# equaliser_TDA7418.net
KiCad netlist of a schematic drawn in EAGLE
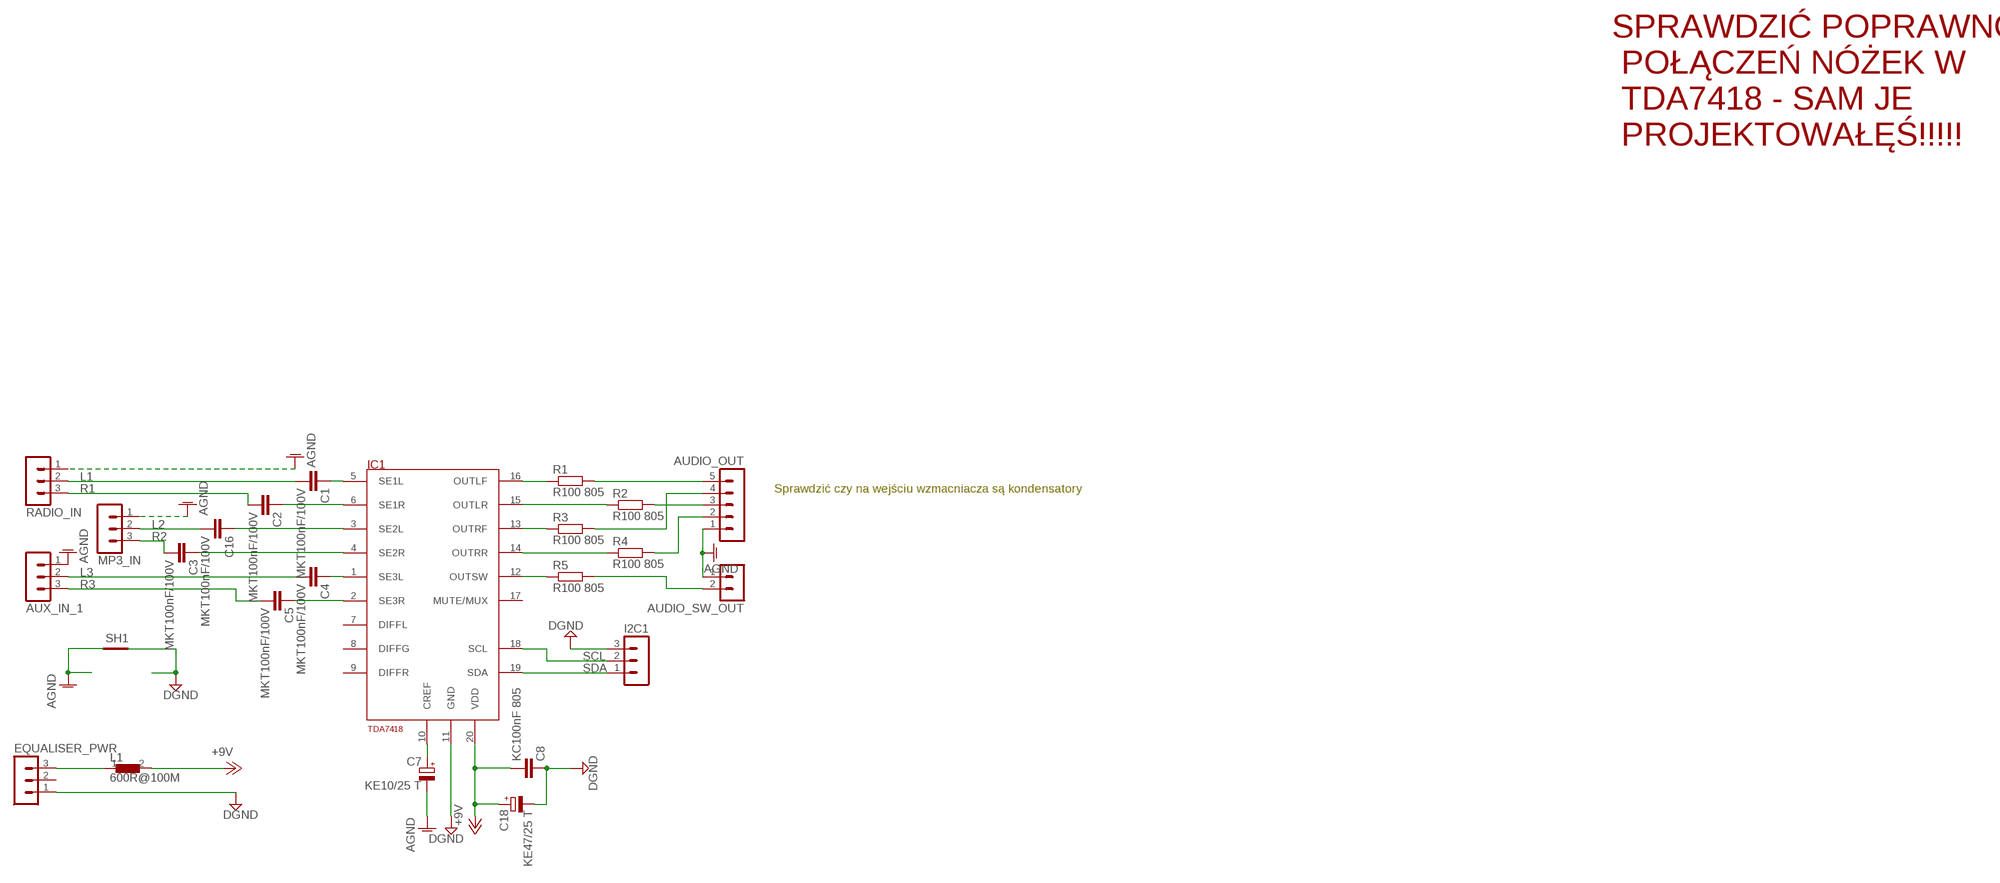
[diagram p0: schematic, sheet 1]

(export (version "E")
  (design (tool "Eeschema 10.0.6"))
  (components
    (comp (ref "AUDIO_OUT")
      (value "MA05-1")
      (footprint "eagle-import:MA05-1")
      (fields (field (name "OC_FARNELL") "unknown") (field (name "OC_NEWARK") "unknown"))
      (libsource (lib "eagle-import") (part "MA05-1"))
    )
    (comp (ref "AUDIO_SW_OUT")
      (value "MA02-1")
      (footprint "eagle-import:MA02-1")
      (libsource (lib "eagle-import") (part "MA02-1"))
    )
    (comp (ref "AUX_IN_1")
      (value "MA03-1")
      (footprint "eagle-import:MA03-1")
      (fields (field (name "OC_FARNELL") "unknown") (field (name "OC_NEWARK") "unknown"))
      (libsource (lib "eagle-import") (part "MA03-1"))
    )
    (comp (ref "C1")
      (value "MKT100nF/100V")
      (footprint "eagle-import:C050-035X075")
      (libsource (lib "eagle-import") (part "C-EU050-035X075"))
    )
    (comp (ref "C2")
      (value "MKT100nF/100V")
      (footprint "eagle-import:C050-035X075")
      (libsource (lib "eagle-import") (part "C-EU050-035X075"))
    )
    (comp (ref "C3")
      (value "MKT100nF/100V")
      (footprint "eagle-import:C050-035X075")
      (libsource (lib "eagle-import") (part "C-EU050-035X075"))
    )
    (comp (ref "C4")
      (value "MKT100nF/100V")
      (footprint "eagle-import:C050-035X075")
      (libsource (lib "eagle-import") (part "C-EU050-035X075"))
    )
    (comp (ref "C5")
      (value "MKT100nF/100V")
      (footprint "eagle-import:C050-035X075")
      (libsource (lib "eagle-import") (part "C-EU050-035X075"))
    )
    (comp (ref "C7")
      (value "KE10/25 T")
      (footprint "eagle-import:E1,8-4")
      (libsource (lib "eagle-import") (part "resistor_CPOL-EUE1.8-4"))
    )
    (comp (ref "C8")
      (value "KC100nF 805")
      (footprint "eagle-import:C0805")
      (libsource (lib "eagle-import") (part "C-EUC0805"))
    )
    (comp (ref "C16")
      (value "MKT100nF/100V")
      (footprint "eagle-import:C050-035X075")
      (libsource (lib "eagle-import") (part "C-EU050-035X075"))
    )
    (comp (ref "C18")
      (value "KE47/25 T")
      (footprint "eagle-import:B45181B")
      (libsource (lib "eagle-import") (part "CPOL-EUB45181B"))
    )
    (comp (ref "EQUALISER_PWR")
      (value "MA03-1")
      (footprint "eagle-import:MA03-1")
      (libsource (lib "eagle-import") (part "MA03-1"))
    )
    (comp (ref "I2C1")
      (value "MA03-1")
      (footprint "eagle-import:MA03-1")
      (libsource (lib "eagle-import") (part "MA03-1"))
    )
    (comp (ref "IC1")
      (value "TDA7418")
      (footprint "eagle-import:SO20")
      (libsource (lib "eagle-import") (part "TDA7418"))
    )
    (comp (ref "L1")
      (value "600R@100M")
      (footprint "eagle-import:R0805")
      (libsource (lib "eagle-import") (part "FERRITR0805"))
    )
    (comp (ref "MP3_IN")
      (value "MA03-1")
      (footprint "eagle-import:MA03-1")
      (fields (field (name "OC_FARNELL") "unknown") (field (name "OC_NEWARK") "unknown"))
      (libsource (lib "eagle-import") (part "MA03-1"))
    )
    (comp (ref "R1")
      (value "R100 805")
      (footprint "eagle-import:0204V")
      (libsource (lib "eagle-import") (part "R-EU_0204/2V"))
    )
    (comp (ref "R2")
      (value "R100 805")
      (footprint "eagle-import:0204V")
      (libsource (lib "eagle-import") (part "R-EU_0204/2V"))
    )
    (comp (ref "R3")
      (value "R100 805")
      (footprint "eagle-import:0204_5")
      (libsource (lib "eagle-import") (part "R-EU_0204/5"))
    )
    (comp (ref "R4")
      (value "R100 805")
      (footprint "eagle-import:0204V")
      (libsource (lib "eagle-import") (part "R-EU_0204/2V"))
    )
    (comp (ref "R5")
      (value "R100 805")
      (footprint "eagle-import:0204V")
      (libsource (lib "eagle-import") (part "R-EU_0204/2V"))
    )
    (comp (ref "RADIO_IN")
      (value "MA03-1")
      (footprint "eagle-import:MA03-1")
      (fields (field (name "OC_FARNELL") "unknown") (field (name "OC_NEWARK") "unknown"))
      (libsource (lib "eagle-import") (part "MA03-1"))
    )
    (comp (ref "SH1")
      (value "SHORT-HT5")
      (footprint "eagle-import:SHORT_TOP-50")
      (libsource (lib "eagle-import") (part "SHORT-HT5"))
    )
  )
  (nets
    (net (code "1") (name "+9V") (class "Default")
      (node (ref "C18") (pin "+") (pinfunction "+_+") (pintype "passive"))
      (node (ref "C8") (pin "2") (pinfunction "2_2") (pintype "passive"))
      (node (ref "IC1") (pin "20") (pinfunction "VDD_20") (pintype "bidirectional"))
      (node (ref "L1") (pin "2") (pinfunction "2_2") (pintype "passive"))
    )
    (net (code "2") (name "/L1") (class "Default")
      (node (ref "C1") (pin "2") (pinfunction "2_2") (pintype "passive"))
      (node (ref "RADIO_IN") (pin "2") (pinfunction "2_2") (pintype "passive"))
    )
    (net (code "3") (name "/L2") (class "Default")
      (node (ref "C16") (pin "2") (pinfunction "2_2") (pintype "passive"))
      (node (ref "MP3_IN") (pin "2") (pinfunction "2_2") (pintype "passive"))
    )
    (net (code "4") (name "/L3") (class "Default")
      (node (ref "AUX_IN_1") (pin "2") (pinfunction "2_2") (pintype "passive"))
      (node (ref "C4") (pin "2") (pinfunction "2_2") (pintype "passive"))
    )
    (net (code "5") (name "/R1") (class "Default")
      (node (ref "C2") (pin "2") (pinfunction "2_2") (pintype "passive"))
      (node (ref "RADIO_IN") (pin "3") (pinfunction "3_3") (pintype "passive"))
    )
    (net (code "6") (name "/R2") (class "Default")
      (node (ref "C3") (pin "2") (pinfunction "2_2") (pintype "passive"))
      (node (ref "MP3_IN") (pin "3") (pinfunction "3_3") (pintype "passive"))
    )
    (net (code "7") (name "/R3") (class "Default")
      (node (ref "AUX_IN_1") (pin "3") (pinfunction "3_3") (pintype "passive"))
      (node (ref "C5") (pin "2") (pinfunction "2_2") (pintype "passive"))
    )
    (net (code "8") (name "/SCL") (class "Default")
      (node (ref "I2C1") (pin "2") (pinfunction "2_2") (pintype "passive"))
      (node (ref "IC1") (pin "18") (pinfunction "SCL_18") (pintype "bidirectional"))
    )
    (net (code "9") (name "/SDA") (class "Default")
      (node (ref "I2C1") (pin "1") (pinfunction "1_1") (pintype "passive"))
      (node (ref "IC1") (pin "19") (pinfunction "SDA_19") (pintype "bidirectional"))
    )
    (net (code "10") (name "AGND") (class "Default")
      (node (ref "AUDIO_OUT") (pin "1") (pinfunction "1_1") (pintype "passive"))
      (node (ref "AUDIO_SW_OUT") (pin "1") (pinfunction "1_1") (pintype "passive"))
      (node (ref "AUX_IN_1") (pin "1") (pinfunction "1_1") (pintype "passive"))
      (node (ref "C7") (pin "-") (pinfunction "-_-") (pintype "passive"))
      (node (ref "MP3_IN") (pin "1") (pinfunction "1_1") (pintype "passive"))
      (node (ref "RADIO_IN") (pin "1") (pinfunction "1_1") (pintype "passive"))
      (node (ref "SH1") (pin "1") (pinfunction "P$1_1") (pintype "bidirectional"))
    )
    (net (code "11") (name "DGND") (class "Default")
      (node (ref "C18") (pin "-") (pinfunction "-_-") (pintype "passive"))
      (node (ref "C8") (pin "1") (pinfunction "1_1") (pintype "passive"))
      (node (ref "EQUALISER_PWR") (pin "1") (pinfunction "1_1") (pintype "passive"))
      (node (ref "I2C1") (pin "3") (pinfunction "3_3") (pintype "passive"))
      (node (ref "IC1") (pin "11") (pinfunction "GND_11") (pintype "bidirectional"))
      (node (ref "SH1") (pin "2") (pinfunction "P$2_2") (pintype "bidirectional"))
    )
    (net (code "12") (name "Net-(AUDIO_OUT-Pad2)") (class "Default")
      (node (ref "AUDIO_OUT") (pin "2") (pinfunction "2_2") (pintype "passive"))
      (node (ref "R4") (pin "2") (pinfunction "2_2") (pintype "passive"))
    )
    (net (code "13") (name "Net-(AUDIO_OUT-Pad3)") (class "Default")
      (node (ref "AUDIO_OUT") (pin "3") (pinfunction "3_3") (pintype "passive"))
      (node (ref "R2") (pin "2") (pinfunction "2_2") (pintype "passive"))
    )
    (net (code "14") (name "Net-(AUDIO_OUT-Pad4)") (class "Default")
      (node (ref "AUDIO_OUT") (pin "4") (pinfunction "4_4") (pintype "passive"))
      (node (ref "R3") (pin "2") (pinfunction "2_2") (pintype "passive"))
    )
    (net (code "15") (name "Net-(AUDIO_OUT-Pad5)") (class "Default")
      (node (ref "AUDIO_OUT") (pin "5") (pinfunction "5_5") (pintype "passive"))
      (node (ref "R1") (pin "2") (pinfunction "2_2") (pintype "passive"))
    )
    (net (code "16") (name "Net-(AUDIO_SW_OUT-Pad2)") (class "Default")
      (node (ref "AUDIO_SW_OUT") (pin "2") (pinfunction "2_2") (pintype "passive"))
      (node (ref "R5") (pin "2") (pinfunction "2_2") (pintype "passive"))
    )
    (net (code "17") (name "Net-(EQUALISER_PWR-Pad3)") (class "Default")
      (node (ref "EQUALISER_PWR") (pin "3") (pinfunction "3_3") (pintype "passive"))
      (node (ref "L1") (pin "1") (pinfunction "1_1") (pintype "passive"))
    )
    (net (code "18") (name "Net-(IC1-CREF)") (class "Default")
      (node (ref "C7") (pin "+") (pinfunction "+_+") (pintype "passive"))
      (node (ref "IC1") (pin "10") (pinfunction "CREF_10") (pintype "bidirectional"))
    )
    (net (code "19") (name "Net-(IC1-OUTLF)") (class "Default")
      (node (ref "IC1") (pin "16") (pinfunction "OUTLF_16") (pintype "bidirectional"))
      (node (ref "R1") (pin "1") (pinfunction "1_1") (pintype "passive"))
    )
    (net (code "20") (name "Net-(IC1-OUTLR)") (class "Default")
      (node (ref "IC1") (pin "15") (pinfunction "OUTLR_15") (pintype "bidirectional"))
      (node (ref "R2") (pin "1") (pinfunction "1_1") (pintype "passive"))
    )
    (net (code "21") (name "Net-(IC1-OUTRF)") (class "Default")
      (node (ref "IC1") (pin "13") (pinfunction "OUTRF_13") (pintype "bidirectional"))
      (node (ref "R3") (pin "1") (pinfunction "1_1") (pintype "passive"))
    )
    (net (code "22") (name "Net-(IC1-OUTRR)") (class "Default")
      (node (ref "IC1") (pin "14") (pinfunction "OUTRR_14") (pintype "bidirectional"))
      (node (ref "R4") (pin "1") (pinfunction "1_1") (pintype "passive"))
    )
    (net (code "23") (name "Net-(IC1-OUTSW)") (class "Default")
      (node (ref "IC1") (pin "12") (pinfunction "OUTSW_12") (pintype "bidirectional"))
      (node (ref "R5") (pin "1") (pinfunction "1_1") (pintype "passive"))
    )
    (net (code "24") (name "Net-(IC1-SE1L)") (class "Default")
      (node (ref "C1") (pin "1") (pinfunction "1_1") (pintype "passive"))
      (node (ref "IC1") (pin "5") (pinfunction "SE1L_5") (pintype "bidirectional"))
    )
    (net (code "25") (name "Net-(IC1-SE1R)") (class "Default")
      (node (ref "C2") (pin "1") (pinfunction "1_1") (pintype "passive"))
      (node (ref "IC1") (pin "6") (pinfunction "SE1R_6") (pintype "bidirectional"))
    )
    (net (code "26") (name "Net-(IC1-SE2L)") (class "Default")
      (node (ref "C16") (pin "1") (pinfunction "1_1") (pintype "passive"))
      (node (ref "IC1") (pin "3") (pinfunction "SE2L_3") (pintype "bidirectional"))
    )
    (net (code "27") (name "Net-(IC1-SE2R)") (class "Default")
      (node (ref "C3") (pin "1") (pinfunction "1_1") (pintype "passive"))
      (node (ref "IC1") (pin "4") (pinfunction "SE2R_4") (pintype "bidirectional"))
    )
    (net (code "28") (name "Net-(IC1-SE3L)") (class "Default")
      (node (ref "C4") (pin "1") (pinfunction "1_1") (pintype "passive"))
      (node (ref "IC1") (pin "1") (pinfunction "SE3L_1") (pintype "bidirectional"))
    )
    (net (code "29") (name "Net-(IC1-SE3R)") (class "Default")
      (node (ref "C5") (pin "1") (pinfunction "1_1") (pintype "passive"))
      (node (ref "IC1") (pin "2") (pinfunction "SE3R_2") (pintype "bidirectional"))
    )
    (net (code "30") (name "unconnected-(EQUALISER_PWR-Pad2)") (class "Default")
      (node (ref "EQUALISER_PWR") (pin "2") (pinfunction "2_2") (pintype "passive"))
    )
    (net (code "31") (name "unconnected-(IC1-DIFFG-Pad8)") (class "Default")
      (node (ref "IC1") (pin "8") (pinfunction "DIFFG_8") (pintype "bidirectional"))
    )
    (net (code "32") (name "unconnected-(IC1-DIFFL-Pad7)") (class "Default")
      (node (ref "IC1") (pin "7") (pinfunction "DIFFL_7") (pintype "bidirectional"))
    )
    (net (code "33") (name "unconnected-(IC1-DIFFR-Pad9)") (class "Default")
      (node (ref "IC1") (pin "9") (pinfunction "DIFFR_9") (pintype "bidirectional"))
    )
    (net (code "34") (name "unconnected-(IC1-MUTE{slash}MUX-Pad17)") (class "Default")
      (node (ref "IC1") (pin "17") (pinfunction "MUTE/MUX_17") (pintype "bidirectional"))
    )
  )
)
